# Sheet-SWITCH-V1_0.net
KiCad netlist of a schematic drawn in Altium Designer
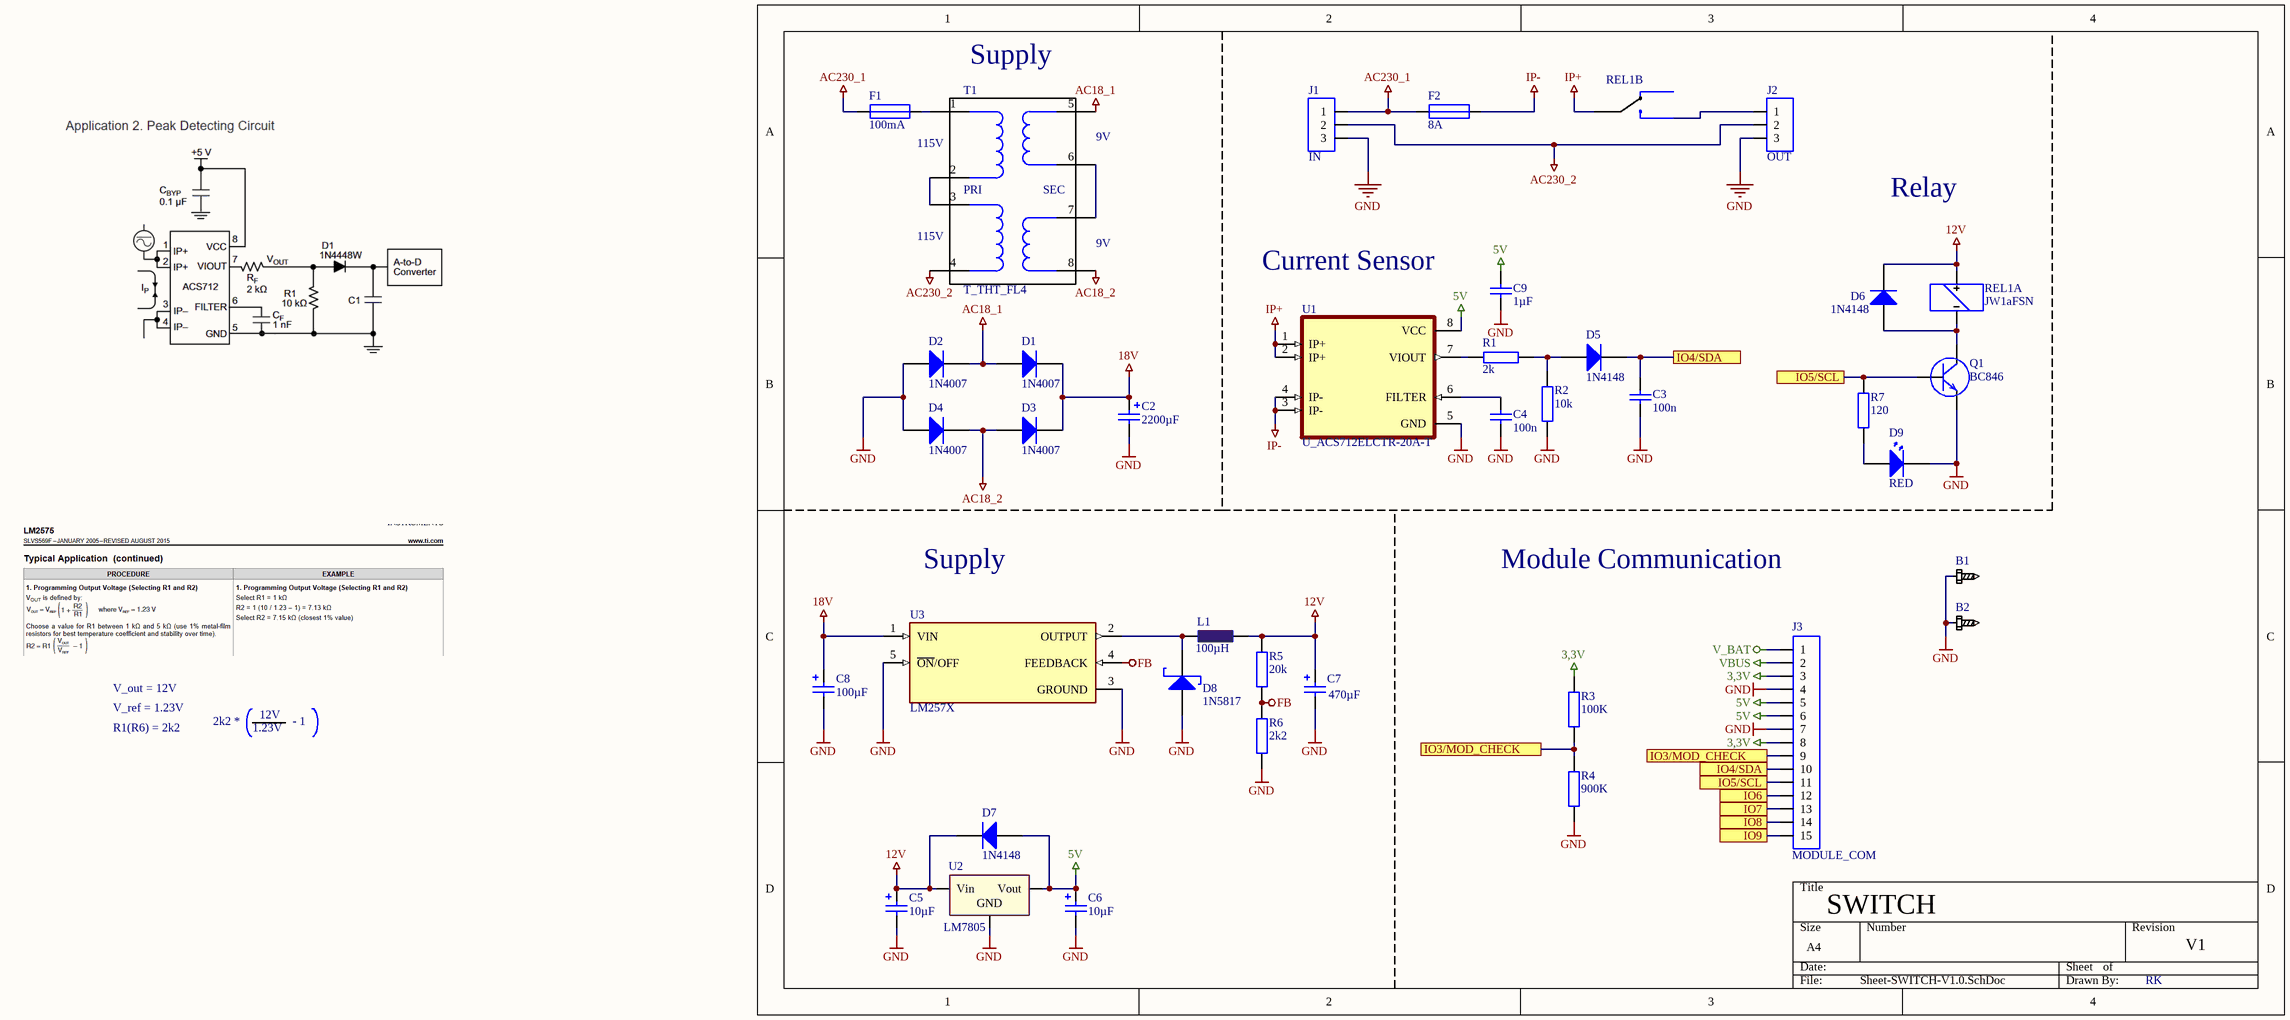
[diagram p0: Sheet-SWITCH-V1.0.SchDoc]

(export (version "E")
  (design (tool "Eeschema 10.0.6"))
  (components
    (comp (ref "B1")
      (value "Schraube")
      (footprint "B_Schraube-M3 PAD")
      (description "Schraubenloch für M3 Schrauben")
      (libsource (lib "SCHLIB-PCSB_5.1.3") (part "B_Schraube"))
    )
    (comp (ref "B2")
      (value "Schraube")
      (footprint "B_Schraube-M3 PAD")
      (description "Schraubenloch für M3 Schrauben")
      (libsource (lib "SCHLIB-PCSB_5.1.3") (part "B_Schraube"))
    )
    (comp (ref "C2")
      (value "2200µF")
      (footprint "C_THT_RB-.3/.6")
      (description "THT Elektrolytkondensator")
      (libsource (lib "SCHLIB-PCSB_5.1.3") (part "C_THT_ELK"))
    )
    (comp (ref "C3")
      (value "100n")
      (footprint "C_SMD_0603")
      (description "Kondensator SMD Universal, Keramik, Folie, usw.")
      (libsource (lib "SCHLIB-PCSB_5.1.3") (part "C_SMD_KO"))
    )
    (comp (ref "C4")
      (value "100n")
      (footprint "C_SMD_0603")
      (description "Kondensator SMD Universal, Keramik, Folie, usw.")
      (libsource (lib "SCHLIB-PCSB_5.1.3") (part "C_SMD_KO"))
    )
    (comp (ref "C5")
      (value "10µF")
      (footprint "C_SMD_B-Typ")
      (description "SMD Elektrolytkondensator")
      (libsource (lib "SCHLIB-PCSB_5.1.3") (part "C_SMD_ELK"))
    )
    (comp (ref "C6")
      (value "10µF")
      (footprint "C_SMD_B-Typ")
      (description "SMD Elektrolytkondensator")
      (libsource (lib "SCHLIB-PCSB_5.1.3") (part "C_SMD_ELK"))
    )
    (comp (ref "C7")
      (value "470µF")
      (footprint "C_SMD_B-Typ")
      (description "SMD Elektrolytkondensator")
      (libsource (lib "SCHLIB-PCSB_5.1.3") (part "C_SMD_ELK"))
    )
    (comp (ref "C8")
      (value "100µF")
      (footprint "C_SMD_B-Typ")
      (description "SMD Elektrolytkondensator")
      (libsource (lib "SCHLIB-PCSB_5.1.3") (part "C_SMD_ELK"))
    )
    (comp (ref "C9")
      (value "1µF")
      (footprint "C_SMD_0603")
      (description "Kondensator SMD Universal, Keramik, Folie, usw.")
      (libsource (lib "SCHLIB-PCSB_5.1.3") (part "C_SMD_KO"))
    )
    (comp (ref "D1")
      (value "1N4007")
      (footprint "D_THT_0.4")
      (description "Diode THT Silizium")
      (libsource (lib "SCHLIB-PCSB_5.1.3") (part "D_THT_Silizium"))
    )
    (comp (ref "D2")
      (value "1N4007")
      (footprint "D_THT_0.4")
      (description "Diode THT Silizium")
      (libsource (lib "SCHLIB-PCSB_5.1.3") (part "D_THT_Silizium"))
    )
    (comp (ref "D3")
      (value "1N4007")
      (footprint "D_THT_0.4")
      (description "Diode THT Silizium")
      (libsource (lib "SCHLIB-PCSB_5.1.3") (part "D_THT_Silizium"))
    )
    (comp (ref "D4")
      (value "1N4007")
      (footprint "D_THT_0.4")
      (description "Diode THT Silizium")
      (libsource (lib "SCHLIB-PCSB_5.1.3") (part "D_THT_Silizium"))
    )
    (comp (ref "D5")
      (value "1N4148")
      (footprint "SOD-80-2")
      (description "Diode SMD Silizium")
      (libsource (lib "SCHLIB-PCSB_5.1.3") (part "D_SMD_Silizium"))
    )
    (comp (ref "D6")
      (value "1N4148")
      (footprint "SOD-80-2")
      (description "Diode SMD Silizium")
      (libsource (lib "SCHLIB-PCSB_5.1.3") (part "D_SMD_Silizium"))
    )
    (comp (ref "D7")
      (value "1N4148")
      (footprint "SOD-80-2")
      (description "Diode SMD Silizium")
      (libsource (lib "SCHLIB-PCSB_5.1.3") (part "D_SMD_Silizium"))
    )
    (comp (ref "D8")
      (value "1N5817")
      (footprint "D_THT_0.6")
      (description "Diode THT Schottky")
      (libsource (lib "SCHLIB-PCSB_5.1.3") (part "D_THT_Schottky"))
    )
    (comp (ref "D9")
      (value "RED")
      (footprint "D_THT_LED-3")
      (description "Diode THT LED")
      (libsource (lib "SCHLIB-PCSB_5.1.3") (part "D_THT_LED"))
    )
    (comp (ref "F1")
      (value "100mA")
      (footprint "F_THT_Fuse2pol")
      (description "Sicherung")
      (libsource (lib "SCHLIB-PCSB_5.1.3") (part "F_THT_Fuse"))
    )
    (comp (ref "F2")
      (value "8A")
      (footprint "F_THT_Fuse2pol")
      (description "Sicherung")
      (libsource (lib "SCHLIB-PCSB_5.1.3") (part "F_THT_Fuse"))
    )
    (comp (ref "J1")
      (value "IN")
      (footprint "J_THT_Printklemme 3x")
      (description "Stecker")
      (libsource (lib "SCHLIB-PCSB_5.1.3") (part "J_THT_CON3"))
    )
    (comp (ref "J2")
      (value "OUT")
      (footprint "J_THT_Printklemme 3x")
      (description "Stecker")
      (libsource (lib "") (part "J_THT_CON3_1"))
    )
    (comp (ref "J3")
      (value "MODULE_COM")
      (footprint "SIP-15_Node_V2")
      (description "Stecker")
      (libsource (lib "SCHLIB-PCSB_5.1.3") (part "J_THT_NODE_V2"))
    )
    (comp (ref "L1")
      (value "100µH")
      (footprint "L_SMD_NPIS42LS")
      (description "Spule SMD")
      (libsource (lib "SCHLIB-PCSB_5.1.3") (part "L_SMD_Spule"))
    )
    (comp (ref "Q1")
      (value "BC846")
      (footprint "SOT-23-3_BC846")
      (description "NPN Transistor")
      (libsource (lib "SCHLIB-PCSB_5.1.3") (part "Q_SMD_NPN"))
    )
    (comp (ref "R1")
      (value "2k")
      (footprint "R_SMD_0805")
      (description "Widerstand SMD")
      (libsource (lib "SCHLIB-PCSB_5.1.3") (part "R_SMD_Widerstand"))
    )
    (comp (ref "R2")
      (value "10k")
      (footprint "R_SMD_0805")
      (description "Widerstand SMD")
      (libsource (lib "SCHLIB-PCSB_5.1.3") (part "R_SMD_Widerstand"))
    )
    (comp (ref "R3")
      (value "100K")
      (footprint "R_SMD_0805")
      (description "Widerstand SMD")
      (libsource (lib "SCHLIB-PCSB_5.1.3") (part "R_SMD_Widerstand"))
    )
    (comp (ref "R4")
      (value "900K")
      (footprint "R_SMD_0805")
      (description "Widerstand SMD")
      (libsource (lib "SCHLIB-PCSB_5.1.3") (part "R_SMD_Widerstand"))
    )
    (comp (ref "R5")
      (value "20k")
      (footprint "R_SMD_0805")
      (description "Widerstand SMD")
      (libsource (lib "SCHLIB-PCSB_5.1.3") (part "R_SMD_Widerstand"))
    )
    (comp (ref "R6")
      (value "2k2")
      (footprint "R_SMD_0805")
      (description "Widerstand SMD")
      (libsource (lib "SCHLIB-PCSB_5.1.3") (part "R_SMD_Widerstand"))
    )
    (comp (ref "R7")
      (value "120")
      (footprint "R_SMD_0805")
      (description "Widerstand SMD")
      (libsource (lib "SCHLIB-PCSB_5.1.3") (part "R_SMD_Widerstand"))
    )
    (comp (ref "REL1")
      (value "JW1aFSN")
      (footprint "Rel_THT_1x 2")
      (description "Relais 1 Öffner, 1 Schließer")
      (libsource (lib "SCHLIB-PCSB_5.1.3") (part "Rel_THT_1x2"))
    )
    (comp (ref "T1")
      (value "T_THT_FL4")
      (footprint "FL_4_Trafo")
      (description "Flachtrafo von Block 4VA\r\n2x Primär\r\n2x Sekundär")
      (libsource (lib "SCHLIB-PCSB_5.1.3") (part "T_THT_FL4"))
    )
    (comp (ref "U1")
      (value "U_ACS712ELCTR-20A-T")
      (footprint "SO-8")
      (description "Current Sensor 20A 1 Channel Hall Effect, Open Loop Bidirectional 8-SOIC (0.154, 3.90mm Width)")
      (fields (field (name "MF") "Allegro") (field (name "MP") "ACS712ELCTR-20A-T"))
      (libsource (lib "SCHLIB-PCSB_5.1.3") (part "U_ACS712ELCTR-20A-T"))
    )
    (comp (ref "U2")
      (value "LM7805")
      (footprint "TO-220-3H")
      (description "Linearwandler")
      (libsource (lib "SCHLIB-PCSB_5.1.3") (part "U_THT_78xx"))
    )
    (comp (ref "U3")
      (value "LM257X")
      (footprint "TO220-5V")
      (description "Spanungswandler Step Up/Down")
      (libsource (lib "SCHLIB-PCSB_5.1.3") (part "U_THT_LM25xx"))
    )
  )
  (nets
    (net (code "1") (name "/IO3{slash}MOD_CHECK") (class "Default")
      (node (ref "J3") (pin "9") (pinfunction "9_9") (pintype "passive"))
      (node (ref "R3") (pin "1") (pintype "passive"))
      (node (ref "R4") (pin "2") (pintype "passive"))
    )
    (net (code "2") (name "/IO4{slash}SDA") (class "Default")
      (node (ref "C3") (pin "1") (pintype "passive"))
      (node (ref "D5") (pin "2") (pinfunction "K_2") (pintype "passive"))
      (node (ref "J3") (pin "10") (pinfunction "10_10") (pintype "passive"))
    )
    (net (code "3") (name "/IO5{slash}SCL") (class "Default")
      (node (ref "J3") (pin "11") (pinfunction "11_11") (pintype "passive"))
      (node (ref "Q1") (pin "B") (pinfunction "B_B") (pintype "passive"))
      (node (ref "R7") (pin "1") (pintype "passive"))
    )
    (net (code "4") (name "/IO6") (class "Default")
      (node (ref "J3") (pin "12") (pinfunction "12_12") (pintype "passive"))
    )
    (net (code "5") (name "/IO7") (class "Default")
      (node (ref "J3") (pin "13") (pinfunction "13_13") (pintype "passive"))
    )
    (net (code "6") (name "/IO8") (class "Default")
      (node (ref "J3") (pin "14") (pinfunction "14_14") (pintype "passive"))
    )
    (net (code "7") (name "/IO9") (class "Default")
      (node (ref "J3") (pin "15") (pinfunction "15_15") (pintype "passive"))
    )
    (net (code "8") (name "3,3V") (class "Default")
      (node (ref "J3") (pin "3") (pinfunction "3_3") (pintype "passive"))
      (node (ref "J3") (pin "8") (pinfunction "8_8") (pintype "passive"))
      (node (ref "R3") (pin "2") (pintype "passive"))
    )
    (net (code "9") (name "5V") (class "Default")
      (node (ref "C6") (pin "1") (pinfunction "1_1") (pintype "passive"))
      (node (ref "C9") (pin "1") (pintype "passive"))
      (node (ref "D7") (pin "1") (pinfunction "A_1") (pintype "passive"))
      (node (ref "J3") (pin "5") (pinfunction "5_5") (pintype "passive"))
      (node (ref "J3") (pin "6") (pinfunction "6_6") (pintype "passive"))
      (node (ref "U1") (pin "8") (pinfunction "VCC_8") (pintype "power_in"))
      (node (ref "U2") (pin "2") (pinfunction "Vout_2") (pintype "passive"))
    )
    (net (code "10") (name "12V") (class "Default")
      (node (ref "C5") (pin "1") (pinfunction "1_1") (pintype "passive"))
      (node (ref "C7") (pin "1") (pinfunction "1_1") (pintype "passive"))
      (node (ref "D6") (pin "2") (pinfunction "K_2") (pintype "passive"))
      (node (ref "D7") (pin "2") (pinfunction "K_2") (pintype "passive"))
      (node (ref "L1") (pin "1") (pintype "passive"))
      (node (ref "R5") (pin "1") (pintype "passive"))
      (node (ref "REL1") (pin "1") (pinfunction "+_1") (pintype "passive"))
      (node (ref "U2") (pin "1") (pinfunction "Vin_1") (pintype "passive"))
    )
    (net (code "11") (name "18V") (class "Default")
      (node (ref "C2") (pin "1") (pinfunction "1_1") (pintype "passive"))
      (node (ref "C8") (pin "1") (pinfunction "1_1") (pintype "passive"))
      (node (ref "D1") (pin "2") (pinfunction "K_2") (pintype "passive"))
      (node (ref "D3") (pin "2") (pinfunction "K_2") (pintype "passive"))
      (node (ref "U3") (pin "1") (pinfunction "VIN_1") (pintype "input"))
    )
    (net (code "12") (name "AC18_1") (class "Default")
      (node (ref "D1") (pin "1") (pinfunction "A_1") (pintype "passive"))
      (node (ref "D2") (pin "2") (pinfunction "K_2") (pintype "passive"))
      (node (ref "T1") (pin "5") (pinfunction "5_5") (pintype "passive"))
    )
    (net (code "13") (name "AC18_2") (class "Default")
      (node (ref "D3") (pin "1") (pinfunction "A_1") (pintype "passive"))
      (node (ref "D4") (pin "2") (pinfunction "K_2") (pintype "passive"))
      (node (ref "T1") (pin "8") (pinfunction "8_8") (pintype "passive"))
    )
    (net (code "14") (name "AC230_1") (class "Default")
      (node (ref "F1") (pin "1") (pintype "passive"))
      (node (ref "F2") (pin "1") (pintype "passive"))
      (node (ref "J1") (pin "1") (pinfunction "1_1") (pintype "passive"))
    )
    (net (code "15") (name "AC230_2") (class "Default")
      (node (ref "J1") (pin "2") (pinfunction "2_2") (pintype "passive"))
      (node (ref "J2") (pin "2") (pinfunction "2_2") (pintype "passive"))
      (node (ref "T1") (pin "4") (pinfunction "4_4") (pintype "passive"))
    )
    (net (code "16") (name "FB") (class "Default")
      (node (ref "R5") (pin "2") (pintype "passive"))
      (node (ref "R6") (pin "1") (pintype "passive"))
      (node (ref "U3") (pin "4") (pinfunction "FEEDBACK_4") (pintype "input"))
    )
    (net (code "17") (name "GND") (class "Default")
      (node (ref "B1") (pin "1") (pinfunction "PAD_1") (pintype "passive"))
      (node (ref "B2") (pin "1") (pinfunction "PAD_1") (pintype "passive"))
      (node (ref "C2") (pin "2") (pinfunction "2_2") (pintype "passive"))
      (node (ref "C3") (pin "2") (pintype "passive"))
      (node (ref "C4") (pin "2") (pintype "passive"))
      (node (ref "C5") (pin "2") (pinfunction "2_2") (pintype "passive"))
      (node (ref "C6") (pin "2") (pinfunction "2_2") (pintype "passive"))
      (node (ref "C7") (pin "2") (pinfunction "2_2") (pintype "passive"))
      (node (ref "C8") (pin "2") (pinfunction "2_2") (pintype "passive"))
      (node (ref "C9") (pin "2") (pintype "passive"))
      (node (ref "D2") (pin "1") (pinfunction "A_1") (pintype "passive"))
      (node (ref "D4") (pin "1") (pinfunction "A_1") (pintype "passive"))
      (node (ref "D8") (pin "1") (pinfunction "A_1") (pintype "passive"))
      (node (ref "D9") (pin "2") (pinfunction "K_2") (pintype "passive"))
      (node (ref "J1") (pin "3") (pinfunction "3_3") (pintype "passive"))
      (node (ref "J2") (pin "3") (pinfunction "3_3") (pintype "passive"))
      (node (ref "J3") (pin "4") (pinfunction "4_4") (pintype "passive"))
      (node (ref "J3") (pin "7") (pinfunction "7_7") (pintype "passive"))
      (node (ref "Q1") (pin "E") (pinfunction "E_E") (pintype "passive"))
      (node (ref "R2") (pin "2") (pintype "passive"))
      (node (ref "R4") (pin "1") (pintype "passive"))
      (node (ref "R6") (pin "2") (pintype "passive"))
      (node (ref "U1") (pin "5") (pinfunction "GND_5") (pintype "power_in"))
      (node (ref "U2") (pin "3") (pinfunction "GND_3") (pintype "passive"))
      (node (ref "U3") (pin "3") (pinfunction "GROUND_3") (pintype "power_in"))
      (node (ref "U3") (pin "5") (pinfunction "~{ON}/OFF_5") (pintype "input"))
    )
    (net (code "18") (name "IP+") (class "Default")
      (node (ref "REL1") (pin "3") (pinfunction "3_3") (pintype "passive"))
      (node (ref "U1") (pin "1") (pinfunction "IP+_1") (pintype "input"))
      (node (ref "U1") (pin "2") (pinfunction "IP+_2") (pintype "input"))
    )
    (net (code "19") (name "IP-") (class "Default")
      (node (ref "F2") (pin "2") (pinfunction "2_2") (pintype "passive"))
      (node (ref "U1") (pin "3") (pinfunction "IP-_3") (pintype "input"))
      (node (ref "U1") (pin "4") (pinfunction "IP-_4") (pintype "input"))
    )
    (net (code "20") (name "Net-(D5-A)") (class "Default")
      (node (ref "D5") (pin "1") (pinfunction "A_1") (pintype "passive"))
      (node (ref "R1") (pin "1") (pintype "passive"))
      (node (ref "R2") (pin "1") (pintype "passive"))
    )
    (net (code "21") (name "Net-(D6-A)") (class "Default")
      (node (ref "D6") (pin "1") (pinfunction "A_1") (pintype "passive"))
      (node (ref "Q1") (pin "C") (pinfunction "C_C") (pintype "passive"))
      (node (ref "REL1") (pin "2") (pinfunction "2_2") (pintype "passive"))
    )
    (net (code "22") (name "Net-(D8-K)") (class "Default")
      (node (ref "D8") (pin "2") (pinfunction "K_2") (pintype "passive"))
      (node (ref "L1") (pin "2") (pintype "passive"))
      (node (ref "U3") (pin "2") (pinfunction "OUTPUT_2") (pintype "output"))
    )
    (net (code "23") (name "Net-(D9-A)") (class "Default")
      (node (ref "D9") (pin "1") (pinfunction "A_1") (pintype "passive"))
      (node (ref "R7") (pin "2") (pintype "passive"))
    )
    (net (code "24") (name "Net-(F1-Pad2)") (class "Default")
      (node (ref "F1") (pin "2") (pinfunction "2_2") (pintype "passive"))
      (node (ref "T1") (pin "1") (pinfunction "1_1") (pintype "passive"))
    )
    (net (code "25") (name "Net-(REL1B-NO)") (class "Default")
      (node (ref "J2") (pin "1") (pinfunction "1_1") (pintype "passive"))
      (node (ref "REL1") (pin "4") (pinfunction "NO_4") (pintype "passive"))
    )
    (net (code "26") (name "Net-(T1-Pad2)") (class "Default")
      (node (ref "T1") (pin "2") (pinfunction "2_2") (pintype "passive"))
      (node (ref "T1") (pin "3") (pinfunction "3_3") (pintype "passive"))
    )
    (net (code "27") (name "Net-(T1-Pad6)") (class "Default")
      (node (ref "T1") (pin "6") (pinfunction "6_6") (pintype "passive"))
      (node (ref "T1") (pin "7") (pinfunction "7_7") (pintype "passive"))
    )
    (net (code "28") (name "Net-(U1-FILTER)") (class "Default")
      (node (ref "C4") (pin "1") (pintype "passive"))
      (node (ref "U1") (pin "6") (pinfunction "FILTER_6") (pintype "input"))
    )
    (net (code "29") (name "Net-(U1-VIOUT)") (class "Default")
      (node (ref "R1") (pin "2") (pintype "passive"))
      (node (ref "U1") (pin "7") (pinfunction "VIOUT_7") (pintype "output"))
    )
    (net (code "30") (name "VBUS") (class "Default")
      (node (ref "J3") (pin "2") (pinfunction "2_2") (pintype "passive"))
    )
    (net (code "31") (name "V_BAT") (class "Default")
      (node (ref "J3") (pin "1") (pinfunction "1_1") (pintype "passive"))
    )
    (net (code "32") (name "unconnected-(REL1-Pad5)") (class "Default")
      (node (ref "REL1") (pin "5") (pinfunction "5_5") (pintype "passive"))
    )
  )
)
